# Schematic.net
KiCad netlist of a schematic drawn in EAGLE
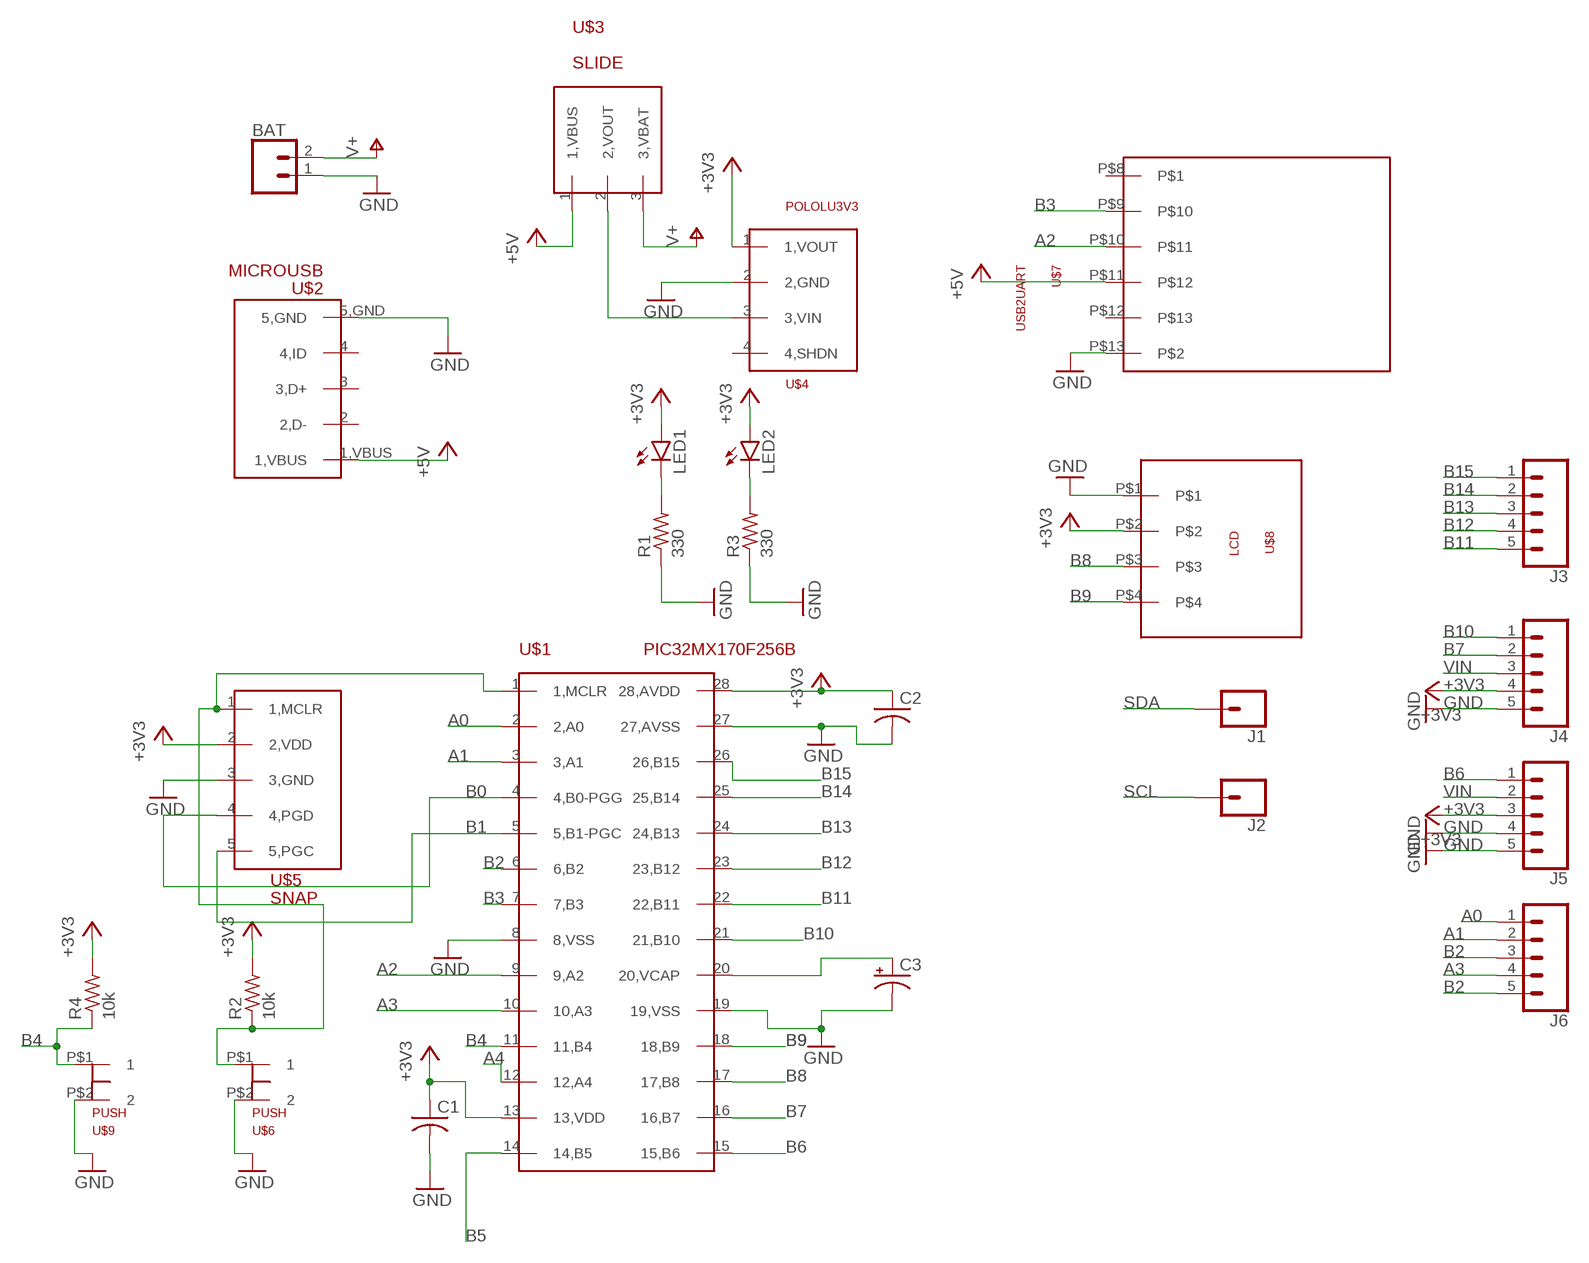
[diagram p0: schematic, sheet 1]

(export (version "E")
  (design (tool "Eeschema 10.0.6"))
  (components
    (comp (ref "BAT")
      (value "CONN_02")
      (footprint "eagle-import:1X02")
      (libsource (lib "eagle-import") (part "CONN_02"))
    )
    (comp (ref "C1")
      (value "C-US025-030X050")
      (footprint "eagle-import:C025-030X050")
      (libsource (lib "eagle-import") (part "C-US025-030X050"))
    )
    (comp (ref "C2")
      (value "C-US025-030X050")
      (footprint "eagle-import:C025-030X050")
      (libsource (lib "eagle-import") (part "C-US025-030X050"))
    )
    (comp (ref "C3")
      (value "CPOL-USB45181B")
      (footprint "eagle-import:B45181B")
      (libsource (lib "eagle-import") (part "CPOL-USB45181B"))
    )
    (comp (ref "J1")
      (value "CONN_01")
      (footprint "eagle-import:1X01")
      (libsource (lib "eagle-import") (part "CONN_01"))
    )
    (comp (ref "J2")
      (value "CONN_01")
      (footprint "eagle-import:1X01")
      (libsource (lib "eagle-import") (part "CONN_01"))
    )
    (comp (ref "J3")
      (value "CONN_05")
      (footprint "eagle-import:1X05")
      (libsource (lib "eagle-import") (part "CONN_05"))
    )
    (comp (ref "J4")
      (value "CONN_05")
      (footprint "eagle-import:1X05")
      (libsource (lib "eagle-import") (part "CONN_05"))
    )
    (comp (ref "J5")
      (value "CONN_05")
      (footprint "eagle-import:1X05")
      (libsource (lib "eagle-import") (part "CONN_05"))
    )
    (comp (ref "J6")
      (value "CONN_05")
      (footprint "eagle-import:1X05")
      (libsource (lib "eagle-import") (part "CONN_05"))
    )
    (comp (ref "LED1")
      (value "LED3MM")
      (footprint "eagle-import:LED3MM")
      (libsource (lib "eagle-import") (part "LED3MM"))
    )
    (comp (ref "LED2")
      (value "LED3MM")
      (footprint "eagle-import:LED3MM")
      (libsource (lib "eagle-import") (part "LED3MM"))
    )
    (comp (ref "R1")
      (value "330")
      (footprint "eagle-import:0207_10")
      (libsource (lib "eagle-import") (part "R-US_0207/10"))
    )
    (comp (ref "R2")
      (value "10k")
      (footprint "eagle-import:0207_10")
      (libsource (lib "eagle-import") (part "R-US_0207/10"))
    )
    (comp (ref "R3")
      (value "330")
      (footprint "eagle-import:0207_10")
      (libsource (lib "eagle-import") (part "R-US_0207/10"))
    )
    (comp (ref "R4")
      (value "10k")
      (footprint "eagle-import:0207_10")
      (libsource (lib "eagle-import") (part "R-US_0207/10"))
    )
    (comp (ref "U$1")
      (value "PIC32MX170F256B")
      (footprint "eagle-import:DIL28-3")
      (libsource (lib "eagle-import") (part "PIC32MX170F256B"))
    )
    (comp (ref "U$2")
      (value "MICROUSB")
      (footprint "eagle-import:MICROUSB")
      (libsource (lib "eagle-import") (part "MICROUSB"))
    )
    (comp (ref "U$3")
      (value "SLIDE")
      (footprint "eagle-import:SLIDE")
      (libsource (lib "eagle-import") (part "SLIDE"))
    )
    (comp (ref "U$4")
      (value "POLOLU3V3")
      (footprint "eagle-import:POLOLU3V3")
      (libsource (lib "eagle-import") (part "POLOLU3V3"))
    )
    (comp (ref "U$5")
      (value "SNAP")
      (footprint "eagle-import:SNAP")
      (libsource (lib "eagle-import") (part "SNAP"))
    )
    (comp (ref "U$6")
      (value "PUSH")
      (footprint "eagle-import:PUSH")
      (libsource (lib "eagle-import") (part "PUSH"))
    )
    (comp (ref "U$7")
      (value "USB2UART")
      (footprint "eagle-import:USB2UART")
      (libsource (lib "eagle-import") (part "USB2UART"))
    )
    (comp (ref "U$8")
      (value "LCD")
      (footprint "eagle-import:LCD")
      (libsource (lib "eagle-import") (part "LCD"))
    )
    (comp (ref "U$9")
      (value "PUSH")
      (footprint "eagle-import:PUSH")
      (libsource (lib "eagle-import") (part "PUSH"))
    )
  )
  (nets
    (net (code "1") (name "+3V3") (class "Default")
      (node (ref "C1") (pin "1") (pinfunction "1_1") (pintype "passive"))
      (node (ref "C2") (pin "1") (pinfunction "1_1") (pintype "passive"))
      (node (ref "J4") (pin "4") (pinfunction "4_4") (pintype "passive"))
      (node (ref "J5") (pin "3") (pinfunction "3_3") (pintype "passive"))
      (node (ref "LED1") (pin "A") (pinfunction "A_A") (pintype "passive"))
      (node (ref "LED2") (pin "A") (pinfunction "A_A") (pintype "passive"))
      (node (ref "R2") (pin "2") (pinfunction "2_2") (pintype "passive"))
      (node (ref "R4") (pin "2") (pinfunction "2_2") (pintype "passive"))
      (node (ref "U$1") (pin "13") (pinfunction "13,VDD_13") (pintype "bidirectional"))
      (node (ref "U$1") (pin "28") (pinfunction "28,AVDD_28") (pintype "bidirectional"))
      (node (ref "U$4") (pin "1") (pinfunction "1,VOUT_1") (pintype "bidirectional"))
      (node (ref "U$5") (pin "2") (pinfunction "2,VDD_2") (pintype "bidirectional"))
      (node (ref "U$8") (pin "P$2") (pinfunction "P$2_P$2") (pintype "bidirectional"))
    )
    (net (code "2") (name "+5V") (class "Default")
      (node (ref "U$2") (pin "1,VBUS") (pinfunction "1,VBUS_1,VBUS") (pintype "bidirectional"))
      (node (ref "U$3") (pin "1") (pinfunction "1,VBUS_1") (pintype "bidirectional"))
      (node (ref "U$7") (pin "P$11") (pinfunction "P$12_P$11") (pintype "bidirectional"))
    )
    (net (code "3") (name "/A0") (class "Default")
      (node (ref "J6") (pin "1") (pinfunction "1_1") (pintype "passive"))
      (node (ref "U$1") (pin "2") (pinfunction "2,A0_2") (pintype "bidirectional"))
    )
    (net (code "4") (name "/A1") (class "Default")
      (node (ref "J6") (pin "2") (pinfunction "2_2") (pintype "passive"))
      (node (ref "U$1") (pin "3") (pinfunction "3,A1_3") (pintype "bidirectional"))
    )
    (net (code "5") (name "/A2") (class "Default")
      (node (ref "U$1") (pin "9") (pinfunction "9,A2_9") (pintype "bidirectional"))
      (node (ref "U$7") (pin "P$10") (pinfunction "P$11_P$10") (pintype "bidirectional"))
    )
    (net (code "6") (name "/A3") (class "Default")
      (node (ref "J6") (pin "4") (pinfunction "4_4") (pintype "passive"))
      (node (ref "U$1") (pin "10") (pinfunction "10,A3_10") (pintype "bidirectional"))
    )
    (net (code "7") (name "/A4") (class "Default")
      (node (ref "U$1") (pin "12") (pinfunction "12,A4_12") (pintype "bidirectional"))
    )
    (net (code "8") (name "/B0") (class "Default")
      (node (ref "U$1") (pin "4") (pinfunction "4,B0-PGG_4") (pintype "bidirectional"))
      (node (ref "U$5") (pin "4") (pinfunction "4,PGD_4") (pintype "bidirectional"))
    )
    (net (code "9") (name "/B1") (class "Default")
      (node (ref "U$1") (pin "5") (pinfunction "5,B1-PGC_5") (pintype "bidirectional"))
      (node (ref "U$5") (pin "5") (pinfunction "5,PGC_5") (pintype "bidirectional"))
    )
    (net (code "10") (name "/B2") (class "Default")
      (node (ref "J6") (pin "3") (pinfunction "3_3") (pintype "passive"))
      (node (ref "J6") (pin "5") (pinfunction "5_5") (pintype "passive"))
      (node (ref "U$1") (pin "6") (pinfunction "6,B2_6") (pintype "bidirectional"))
    )
    (net (code "11") (name "/B3") (class "Default")
      (node (ref "U$1") (pin "7") (pinfunction "7,B3_7") (pintype "bidirectional"))
      (node (ref "U$7") (pin "P$9") (pinfunction "P$10_P$9") (pintype "bidirectional"))
    )
    (net (code "12") (name "/B4") (class "Default")
      (node (ref "R4") (pin "1") (pinfunction "1_1") (pintype "passive"))
      (node (ref "U$1") (pin "11") (pinfunction "11,B4_11") (pintype "bidirectional"))
      (node (ref "U$9") (pin "P$1") (pinfunction "1_P$1") (pintype "bidirectional"))
    )
    (net (code "13") (name "/B5") (class "Default")
      (node (ref "U$1") (pin "14") (pinfunction "14,B5_14") (pintype "bidirectional"))
    )
    (net (code "14") (name "/B6") (class "Default")
      (node (ref "J5") (pin "1") (pinfunction "1_1") (pintype "passive"))
      (node (ref "U$1") (pin "15") (pinfunction "15,B6_15") (pintype "bidirectional"))
    )
    (net (code "15") (name "/B7") (class "Default")
      (node (ref "J4") (pin "2") (pinfunction "2_2") (pintype "passive"))
      (node (ref "U$1") (pin "16") (pinfunction "16,B7_16") (pintype "bidirectional"))
    )
    (net (code "16") (name "/B8") (class "Default")
      (node (ref "U$1") (pin "17") (pinfunction "17,B8_17") (pintype "bidirectional"))
      (node (ref "U$8") (pin "P$3") (pinfunction "P$3_P$3") (pintype "bidirectional"))
    )
    (net (code "17") (name "/B9") (class "Default")
      (node (ref "U$1") (pin "18") (pinfunction "18,B9_18") (pintype "bidirectional"))
      (node (ref "U$8") (pin "P$4") (pinfunction "P$4_P$4") (pintype "bidirectional"))
    )
    (net (code "18") (name "/B10") (class "Default")
      (node (ref "J4") (pin "1") (pinfunction "1_1") (pintype "passive"))
      (node (ref "U$1") (pin "21") (pinfunction "21,B10_21") (pintype "bidirectional"))
    )
    (net (code "19") (name "/B11") (class "Default")
      (node (ref "J3") (pin "5") (pinfunction "5_5") (pintype "passive"))
      (node (ref "U$1") (pin "22") (pinfunction "22,B11_22") (pintype "bidirectional"))
    )
    (net (code "20") (name "/B12") (class "Default")
      (node (ref "J3") (pin "4") (pinfunction "4_4") (pintype "passive"))
      (node (ref "U$1") (pin "23") (pinfunction "23,B12_23") (pintype "bidirectional"))
    )
    (net (code "21") (name "/B13") (class "Default")
      (node (ref "J3") (pin "3") (pinfunction "3_3") (pintype "passive"))
      (node (ref "U$1") (pin "24") (pinfunction "24,B13_24") (pintype "bidirectional"))
    )
    (net (code "22") (name "/B14") (class "Default")
      (node (ref "J3") (pin "2") (pinfunction "2_2") (pintype "passive"))
      (node (ref "U$1") (pin "25") (pinfunction "25,B14_25") (pintype "bidirectional"))
    )
    (net (code "23") (name "/B15") (class "Default")
      (node (ref "J3") (pin "1") (pinfunction "1_1") (pintype "passive"))
      (node (ref "U$1") (pin "26") (pinfunction "26,B15_26") (pintype "bidirectional"))
    )
    (net (code "24") (name "/SCL") (class "Default")
      (node (ref "J2") (pin "1") (pinfunction "1_1") (pintype "passive"))
    )
    (net (code "25") (name "/SDA") (class "Default")
      (node (ref "J1") (pin "1") (pinfunction "1_1") (pintype "passive"))
    )
    (net (code "26") (name "/VIN") (class "Default")
      (node (ref "J4") (pin "3") (pinfunction "3_3") (pintype "passive"))
      (node (ref "J5") (pin "2") (pinfunction "2_2") (pintype "passive"))
    )
    (net (code "27") (name "GND") (class "Default")
      (node (ref "BAT") (pin "1") (pinfunction "1_1") (pintype "passive"))
      (node (ref "C1") (pin "2") (pinfunction "2_2") (pintype "passive"))
      (node (ref "C2") (pin "2") (pinfunction "2_2") (pintype "passive"))
      (node (ref "C3") (pin "-") (pinfunction "-_-") (pintype "passive"))
      (node (ref "J4") (pin "5") (pinfunction "5_5") (pintype "passive"))
      (node (ref "J5") (pin "4") (pinfunction "4_4") (pintype "passive"))
      (node (ref "J5") (pin "5") (pinfunction "5_5") (pintype "passive"))
      (node (ref "R1") (pin "1") (pinfunction "1_1") (pintype "passive"))
      (node (ref "R3") (pin "1") (pinfunction "1_1") (pintype "passive"))
      (node (ref "U$1") (pin "19") (pinfunction "19,VSS_19") (pintype "bidirectional"))
      (node (ref "U$1") (pin "27") (pinfunction "27,AVSS_27") (pintype "bidirectional"))
      (node (ref "U$1") (pin "8") (pinfunction "8,VSS_8") (pintype "bidirectional"))
      (node (ref "U$2") (pin "5,GND") (pinfunction "5,GND_5,GND") (pintype "bidirectional"))
      (node (ref "U$4") (pin "2") (pinfunction "2,GND_2") (pintype "bidirectional"))
      (node (ref "U$5") (pin "3") (pinfunction "3,GND_3") (pintype "bidirectional"))
      (node (ref "U$6") (pin "P$2") (pinfunction "2_P$2") (pintype "bidirectional"))
      (node (ref "U$7") (pin "P$13") (pinfunction "P$2_P$13") (pintype "bidirectional"))
      (node (ref "U$8") (pin "P$1") (pinfunction "P$1_P$1") (pintype "bidirectional"))
      (node (ref "U$9") (pin "P$2") (pinfunction "2_P$2") (pintype "bidirectional"))
    )
    (net (code "28") (name "Net-(LED1-C)") (class "Default")
      (node (ref "LED1") (pin "K") (pinfunction "C_K") (pintype "passive"))
      (node (ref "R1") (pin "2") (pinfunction "2_2") (pintype "passive"))
    )
    (net (code "29") (name "Net-(LED2-C)") (class "Default")
      (node (ref "LED2") (pin "K") (pinfunction "C_K") (pintype "passive"))
      (node (ref "R3") (pin "2") (pinfunction "2_2") (pintype "passive"))
    )
    (net (code "30") (name "Net-(U$1-1,MCLR)") (class "Default")
      (node (ref "R2") (pin "1") (pinfunction "1_1") (pintype "passive"))
      (node (ref "U$1") (pin "1") (pinfunction "1,MCLR_1") (pintype "bidirectional"))
      (node (ref "U$5") (pin "1") (pinfunction "1,MCLR_1") (pintype "bidirectional"))
      (node (ref "U$6") (pin "P$1") (pinfunction "1_P$1") (pintype "bidirectional"))
    )
    (net (code "31") (name "Net-(U$1-20,VCAP)") (class "Default")
      (node (ref "C3") (pin "+") (pinfunction "+_+") (pintype "passive"))
      (node (ref "U$1") (pin "20") (pinfunction "20,VCAP_20") (pintype "bidirectional"))
    )
    (net (code "32") (name "Net-(U$3-2,VOUT)") (class "Default")
      (node (ref "U$3") (pin "2") (pinfunction "2,VOUT_2") (pintype "bidirectional"))
      (node (ref "U$4") (pin "3") (pinfunction "3,VIN_3") (pintype "bidirectional"))
    )
    (net (code "33") (name "V+") (class "Default")
      (node (ref "BAT") (pin "2") (pinfunction "2_2") (pintype "passive"))
      (node (ref "U$3") (pin "3") (pinfunction "3,VBAT_3") (pintype "bidirectional"))
    )
    (net (code "34") (name "unconnected-(U$2-2,D--Pad2)") (class "Default")
      (node (ref "U$2") (pin "2") (pinfunction "2,D-_2") (pintype "bidirectional"))
    )
    (net (code "35") (name "unconnected-(U$2-3,D+-Pad3)") (class "Default")
      (node (ref "U$2") (pin "3") (pinfunction "3,D+_3") (pintype "bidirectional"))
    )
    (net (code "36") (name "unconnected-(U$2-4,ID-Pad4)") (class "Default")
      (node (ref "U$2") (pin "4") (pinfunction "4,ID_4") (pintype "bidirectional"))
    )
    (net (code "37") (name "unconnected-(U$4-4,SHDN-Pad4)") (class "Default")
      (node (ref "U$4") (pin "4") (pinfunction "4,SHDN_4") (pintype "bidirectional"))
    )
    (net (code "38") (name "unconnected-(U$7-P$1-PadP$8)") (class "Default")
      (node (ref "U$7") (pin "P$8") (pinfunction "P$1_P$8") (pintype "bidirectional"))
    )
    (net (code "39") (name "unconnected-(U$7-P$13-PadP$12)") (class "Default")
      (node (ref "U$7") (pin "P$12") (pinfunction "P$13_P$12") (pintype "bidirectional"))
    )
  )
)
